# BatteryCharger.net
KiCad netlist of a schematic drawn in Altium Designer
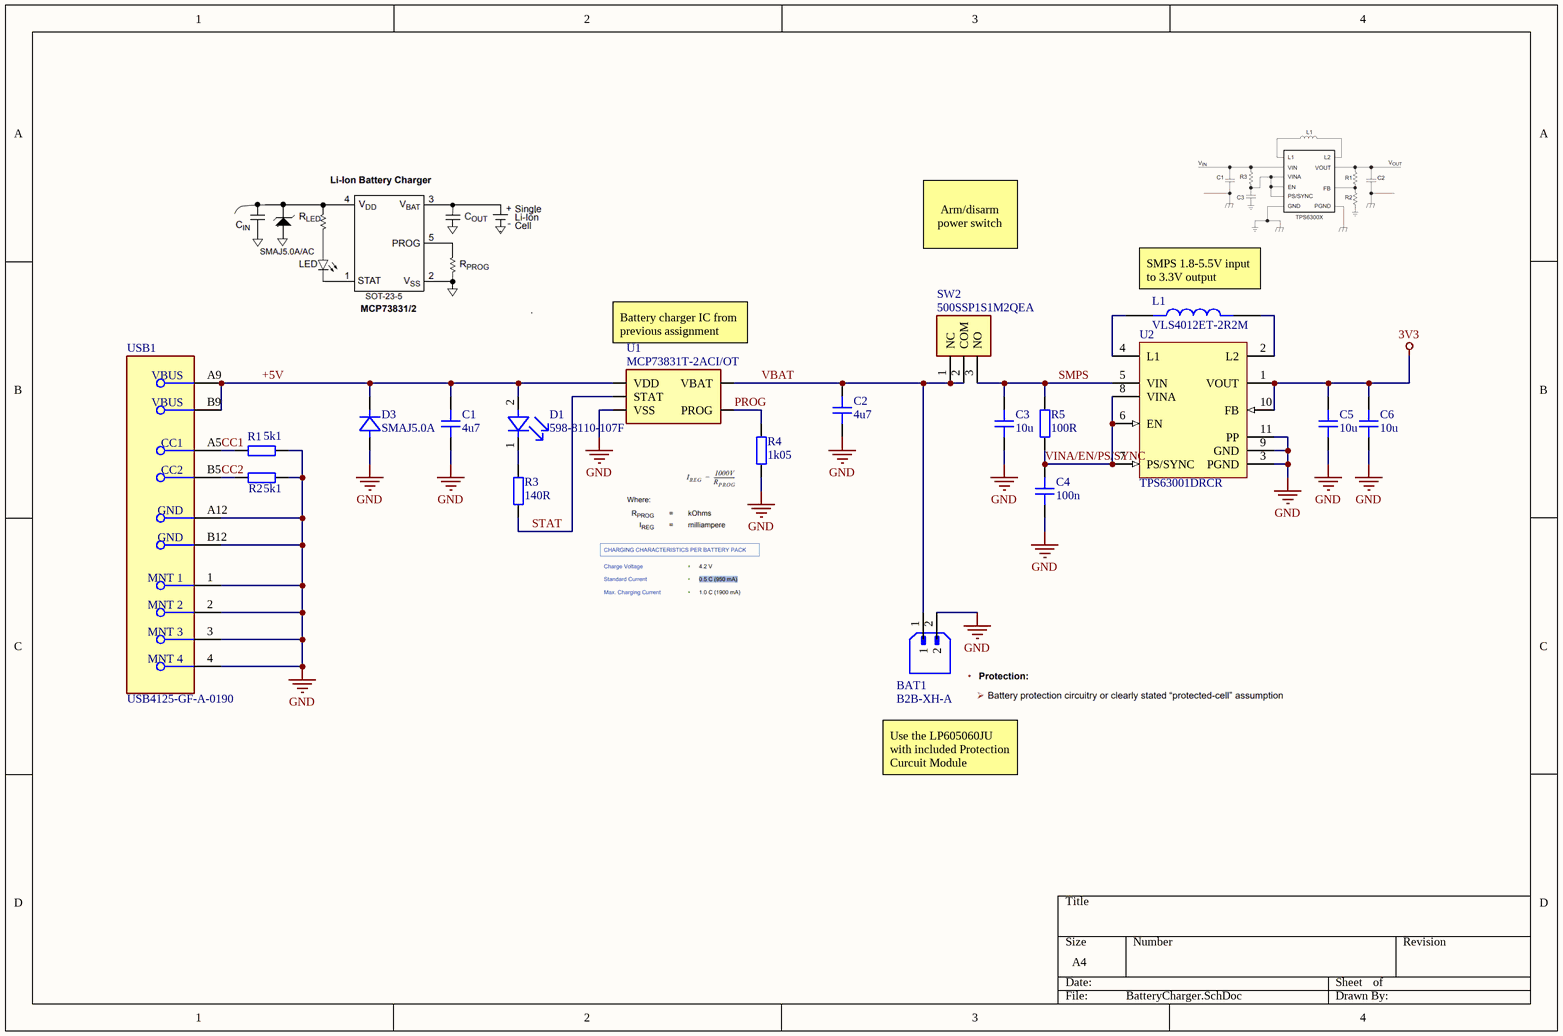
[diagram p0: BatteryCharger.SchDoc]

(export (version "E")
  (design (tool "Eeschema 10.0.6"))
  (components
    (comp (ref "BAT1")
      (value "B2B-XH-A")
      (footprint "JST_B2B-XH-A")
      (fields (field (name "MF") "{'manufacturer': u'JST Sales America Inc.'}"))
      (libsource (lib "Schlib1") (part "B2B-XH-A"))
    )
    (comp (ref "C1")
      (value "4u7")
      (footprint "CAP_0603")
      (description "Capacitor SMD 0603\r\nCeramic")
      (libsource (lib "Generic library") (part "CAP_0603"))
    )
    (comp (ref "C2")
      (value "4u7")
      (footprint "CAP_0603")
      (description "Capacitor SMD 0603\r\nCeramic")
      (libsource (lib "Generic library") (part "CAP_0603"))
    )
    (comp (ref "C3")
      (value "10u")
      (footprint "CAP_0603")
      (description "Capacitor SMD 0603\r\nCeramic")
      (libsource (lib "Generic library") (part "CAP_0603"))
    )
    (comp (ref "C4")
      (value "100n")
      (footprint "CAP_0603")
      (description "Capacitor SMD 0603\r\nCeramic")
      (libsource (lib "Generic library") (part "CAP_0603"))
    )
    (comp (ref "C5")
      (value "10u")
      (footprint "CAP_0603")
      (description "Capacitor SMD 0603\r\nCeramic")
      (libsource (lib "Generic library") (part "CAP_0603"))
    )
    (comp (ref "C6")
      (value "10u")
      (footprint "CAP_0603")
      (description "Capacitor SMD 0603\r\nCeramic")
      (libsource (lib "Generic library") (part "CAP_0603"))
    )
    (comp (ref "D1")
      (value "598-8110-107F")
      (footprint "RED_LED_0805")
      (libsource (lib "Schlib1") (part "RED_LED_0805"))
    )
    (comp (ref "D3")
      (value "SMAJ5.0A")
      (footprint "SMASeries_LTF-M")
      (description "ESD Protection Diode")
      (fields (field (name "COPYRIGHT") "Copyright (C) 2025 Ultra Librarian. All rights reserved."))
      (libsource (lib "Schlib1") (part "SMAJ5.0A"))
    )
    (comp (ref "L1")
      (value "VLS4012ET-2R2M")
      (footprint "IND_VLS4012ET-2R2M")
      (fields (field (name "MF") "TDK"))
      (libsource (lib "Schlib1") (part "VLS4012ET-2R2M"))
    )
    (comp (ref "R1")
      (value "5k1")
      (footprint "RES_0603")
      (description "Resistor SMD 0603")
      (libsource (lib "Generic library") (part "RES_0603"))
    )
    (comp (ref "R2")
      (value "5k1")
      (footprint "RES_0603")
      (description "Resistor SMD 0603")
      (libsource (lib "Schlib1") (part "RES_0603"))
    )
    (comp (ref "R3")
      (value "140R")
      (footprint "RES_0603")
      (description "Resistor SMD 0603")
      (libsource (lib "Generic library") (part "RES_0603"))
    )
    (comp (ref "R4")
      (value "1k05")
      (footprint "RES_0603")
      (description "Resistor SMD 0603")
      (libsource (lib "Schlib1") (part "RES_0603"))
    )
    (comp (ref "R5")
      (value "100R")
      (footprint "RES_0603")
      (description "Resistor SMD 0603")
      (libsource (lib "Generic library") (part "RES_0603"))
    )
    (comp (ref "SW2")
      (value "500SSP1S1M2QEA")
      (footprint "500SSP1S1M2QEA")
      (description "SLIDE, 5A, 120VAC/28VDC SPDT, On-On Through Hole")
      (fields (field (name "MOUSER PART NUMBER") "612-500-A121"))
      (libsource (lib "Schlib1") (part "500SSP1S1M2QEA"))
    )
    (comp (ref "U1")
      (value "MCP73831T-2ACI/OT")
      (footprint "SOT95P270X145-5N")
      (description "Li-Ion Charge Controller 4.2V SOT23-5")
      (fields (field (name "MOUSER PART NUMBER") "579-MCP73831T-2ACIOT"))
      (libsource (lib "Schlib1") (part "MCP73831T-2ACI/OT"))
    )
    (comp (ref "U2")
      (value "TPS63001DRCR")
      (footprint "DRC0010J_V")
      (fields (field (name "MANUFACTURER") "Texas Instruments"))
      (libsource (lib "Altium Content Vault") (part "TI-TPS63001DRC10-3000X1650TP"))
    )
    (comp (ref "USB1")
      (value "USB4125-GF-A-0190")
      (footprint "FP-USB4125-GF-A-0190-MFG")
      (description "CONN RCPT TYPE C 6P SMD RA")
      (libsource (lib "Schlib1") (part "USB type-C"))
    )
  )
  (nets
    (net (code "1") (name "/+5V") (class "Default")
      (node (ref "C1") (pin "2") (pinfunction "2_2") (pintype "passive"))
      (node (ref "D1") (pin "2") (pinfunction "A_2") (pintype "passive"))
      (node (ref "D3") (pin "1") (pinfunction "1_1") (pintype "passive"))
      (node (ref "U1") (pin "4") (pinfunction "VDD_4") (pintype "passive"))
      (node (ref "USB1") (pin "A9") (pinfunction "VBUS_A9") (pintype "passive"))
      (node (ref "USB1") (pin "B9") (pinfunction "VBUS_B9") (pintype "passive"))
    )
    (net (code "2") (name "/CC1") (class "Default")
      (node (ref "R1") (pin "2") (pinfunction "2_2") (pintype "passive"))
      (node (ref "USB1") (pin "A5") (pinfunction "CC1_A5") (pintype "passive"))
    )
    (net (code "3") (name "/CC2") (class "Default")
      (node (ref "R2") (pin "1") (pinfunction "1_1") (pintype "passive"))
      (node (ref "USB1") (pin "B5") (pinfunction "CC2_B5") (pintype "passive"))
    )
    (net (code "4") (name "/PROG") (class "Default")
      (node (ref "R4") (pin "1") (pinfunction "1_1") (pintype "passive"))
      (node (ref "U1") (pin "5") (pinfunction "PROG_5") (pintype "passive"))
    )
    (net (code "5") (name "/SMPS") (class "Default")
      (node (ref "C3") (pin "2") (pinfunction "2_2") (pintype "passive"))
      (node (ref "R5") (pin "2") (pinfunction "2_2") (pintype "passive"))
      (node (ref "SW2") (pin "3") (pinfunction "NO_3") (pintype "passive"))
      (node (ref "U2") (pin "5") (pinfunction "VIN_5") (pintype "power_in"))
    )
    (net (code "6") (name "/STAT") (class "Default")
      (node (ref "R3") (pin "1") (pinfunction "1_1") (pintype "passive"))
      (node (ref "U1") (pin "1") (pinfunction "STAT_1") (pintype "passive"))
    )
    (net (code "7") (name "/VBAT") (class "Default")
      (node (ref "BAT1") (pin "1") (pinfunction "1_1") (pintype "passive"))
      (node (ref "C2") (pin "2") (pinfunction "2_2") (pintype "passive"))
      (node (ref "SW2") (pin "1") (pinfunction "NC_1") (pintype "passive"))
      (node (ref "SW2") (pin "2") (pinfunction "COM_2") (pintype "passive"))
      (node (ref "U1") (pin "3") (pinfunction "VBAT_3") (pintype "passive"))
    )
    (net (code "8") (name "/VINA{slash}EN{slash}PS{slash}SYNC") (class "Default")
      (node (ref "C4") (pin "2") (pinfunction "2_2") (pintype "passive"))
      (node (ref "R5") (pin "1") (pinfunction "1_1") (pintype "passive"))
      (node (ref "U2") (pin "6") (pinfunction "EN_6") (pintype "input"))
      (node (ref "U2") (pin "7") (pinfunction "PS/SYNC_7") (pintype "input"))
      (node (ref "U2") (pin "8") (pinfunction "VINA_8") (pintype "power_in"))
    )
    (net (code "9") (name "3V3") (class "Default")
      (node (ref "C5") (pin "2") (pinfunction "2_2") (pintype "passive"))
      (node (ref "C6") (pin "2") (pinfunction "2_2") (pintype "passive"))
      (node (ref "U2") (pin "1") (pinfunction "VOUT_1") (pintype "power_in"))
      (node (ref "U2") (pin "10") (pinfunction "FB_10") (pintype "input"))
    )
    (net (code "10") (name "GND") (class "Default")
      (node (ref "BAT1") (pin "2") (pinfunction "2_2") (pintype "passive"))
      (node (ref "C1") (pin "1") (pinfunction "1_1") (pintype "passive"))
      (node (ref "C2") (pin "1") (pinfunction "1_1") (pintype "passive"))
      (node (ref "C3") (pin "1") (pinfunction "1_1") (pintype "passive"))
      (node (ref "C4") (pin "1") (pinfunction "1_1") (pintype "passive"))
      (node (ref "C5") (pin "1") (pinfunction "1_1") (pintype "passive"))
      (node (ref "C6") (pin "1") (pinfunction "1_1") (pintype "passive"))
      (node (ref "D3") (pin "2") (pinfunction "2_2") (pintype "passive"))
      (node (ref "R1") (pin "1") (pinfunction "1_1") (pintype "passive"))
      (node (ref "R2") (pin "2") (pinfunction "2_2") (pintype "passive"))
      (node (ref "R4") (pin "2") (pinfunction "2_2") (pintype "passive"))
      (node (ref "U1") (pin "2") (pinfunction "VSS_2") (pintype "passive"))
      (node (ref "U2") (pin "11") (pinfunction "PP_11") (pintype "power_in"))
      (node (ref "U2") (pin "3") (pinfunction "PGND_3") (pintype "power_in"))
      (node (ref "U2") (pin "9") (pinfunction "GND_9") (pintype "power_in"))
      (node (ref "USB1") (pin "1") (pinfunction "MNT_1_1") (pintype "passive"))
      (node (ref "USB1") (pin "2") (pinfunction "MNT_2_2") (pintype "passive"))
      (node (ref "USB1") (pin "3") (pinfunction "MNT_3_3") (pintype "passive"))
      (node (ref "USB1") (pin "4") (pinfunction "MNT_4_4") (pintype "passive"))
      (node (ref "USB1") (pin "A12") (pinfunction "GND_A12") (pintype "passive"))
      (node (ref "USB1") (pin "B12") (pinfunction "GND_B12") (pintype "passive"))
    )
    (net (code "11") (name "Net-(D1-C)") (class "Default")
      (node (ref "D1") (pin "1") (pinfunction "C_1") (pintype "passive"))
      (node (ref "R3") (pin "2") (pinfunction "2_2") (pintype "passive"))
    )
    (net (code "12") (name "Net-(U2-L1)") (class "Default")
      (node (ref "L1") (pin "1") (pinfunction "1_1") (pintype "passive"))
      (node (ref "U2") (pin "4") (pinfunction "L1_4") (pintype "passive"))
    )
    (net (code "13") (name "Net-(U2-L2)") (class "Default")
      (node (ref "L1") (pin "2") (pinfunction "2_2") (pintype "passive"))
      (node (ref "U2") (pin "2") (pinfunction "L2_2") (pintype "passive"))
    )
  )
)
